# biointerfaceController_pcb_Sens.net
KiCad netlist of a schematic drawn in Altium Designer
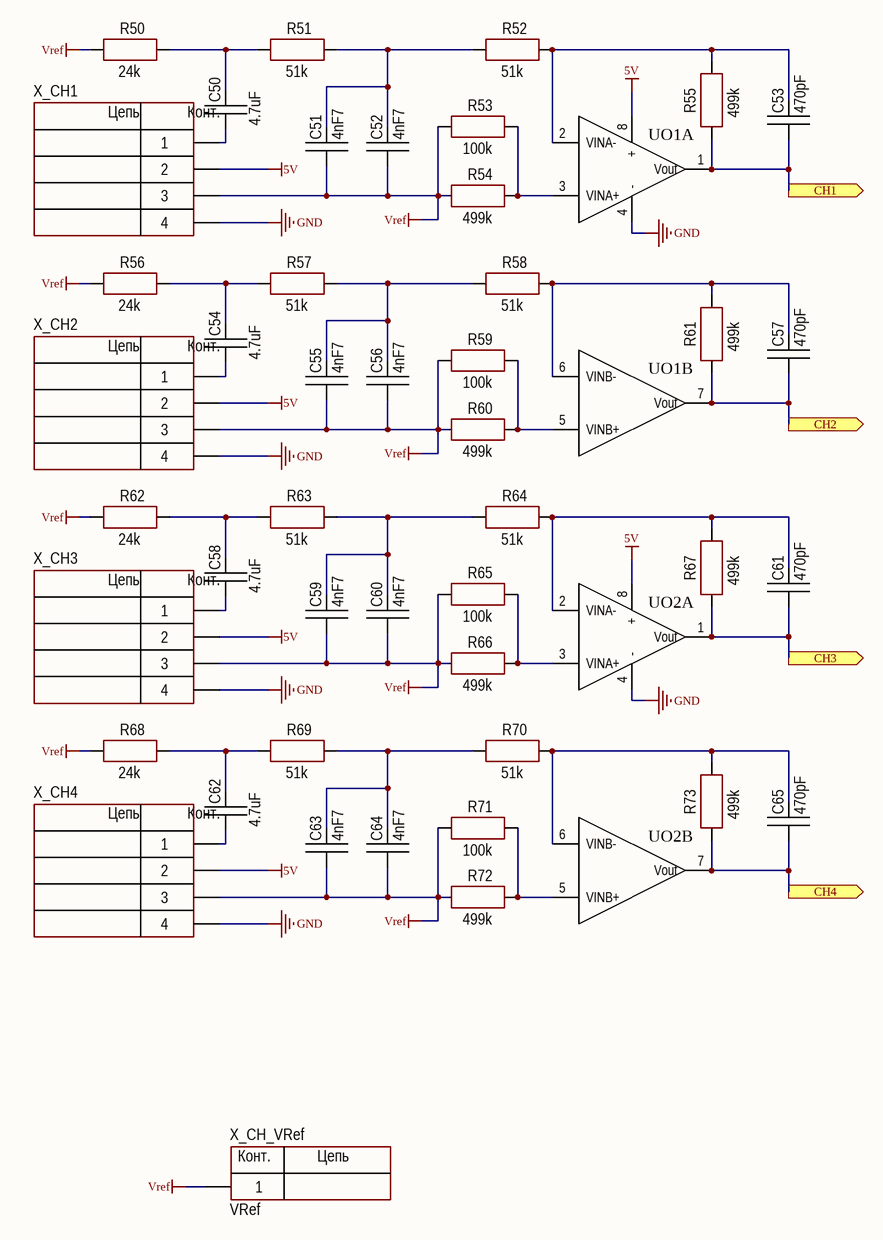
[diagram p0: biointerfaceController_pcb_Sens.SchDoc]

(export (version "E")
  (design (tool "Eeschema 10.0.6"))
  (components
    (comp (ref "C50")
      (value "4.7uF")
      (footprint "SMD-1206C")
      (libsource (lib "biointerfaceController_pcb") (part "Capacitor"))
    )
    (comp (ref "C51") (value "4nF7") (footprint "CH0402C") (libsource (lib "") (part "Capacitor_1")))
    (comp (ref "C52") (value "4nF7") (footprint "CH0402C") (libsource (lib "") (part "Capacitor_1")))
    (comp (ref "C53")
      (value "470pF")
      (footprint "CH0402C")
      (libsource (lib "biointerfaceController_pcb") (part "Capacitor"))
    )
    (comp (ref "C54")
      (value "4.7uF")
      (footprint "SMD-1206C")
      (libsource (lib "biointerfaceController_pcb") (part "Capacitor"))
    )
    (comp (ref "C55")
      (value "4nF7")
      (footprint "CH0402C")
      (libsource (lib "biointerfaceController_pcb") (part "Capacitor"))
    )
    (comp (ref "C56")
      (value "4nF7")
      (footprint "CH0402C")
      (libsource (lib "biointerfaceController_pcb") (part "Capacitor"))
    )
    (comp (ref "C57")
      (value "470pF")
      (footprint "CH0402C")
      (libsource (lib "biointerfaceController_pcb") (part "Capacitor"))
    )
    (comp (ref "C58")
      (value "4.7uF")
      (footprint "SMD-1206C")
      (libsource (lib "biointerfaceController_pcb") (part "Capacitor"))
    )
    (comp (ref "C59")
      (value "4nF7")
      (footprint "CH0402C")
      (libsource (lib "biointerfaceController_pcb") (part "Capacitor"))
    )
    (comp (ref "C60")
      (value "4nF7")
      (footprint "CH0402C")
      (libsource (lib "biointerfaceController_pcb") (part "Capacitor"))
    )
    (comp (ref "C61")
      (value "470pF")
      (footprint "CH0402C")
      (libsource (lib "biointerfaceController_pcb") (part "Capacitor"))
    )
    (comp (ref "C62")
      (value "4.7uF")
      (footprint "SMD-1206C")
      (libsource (lib "biointerfaceController_pcb") (part "Capacitor"))
    )
    (comp (ref "C63")
      (value "4nF7")
      (footprint "CH0402C")
      (libsource (lib "biointerfaceController_pcb") (part "Capacitor"))
    )
    (comp (ref "C64")
      (value "4nF7")
      (footprint "CH0402C")
      (libsource (lib "biointerfaceController_pcb") (part "Capacitor"))
    )
    (comp (ref "C65")
      (value "470pF")
      (footprint "CH0402C")
      (libsource (lib "biointerfaceController_pcb") (part "Capacitor"))
    )
    (comp (ref "R50")
      (value "24k")
      (footprint "CH0402R")
      (libsource (lib "biointerfaceController_pcb") (part "Resistor"))
    )
    (comp (ref "R51")
      (value "51k")
      (footprint "CH0402R")
      (libsource (lib "biointerfaceController_pcb") (part "Resistor"))
    )
    (comp (ref "R52")
      (value "51k")
      (footprint "CH0402R")
      (libsource (lib "biointerfaceController_pcb") (part "Resistor"))
    )
    (comp (ref "R53")
      (value "100k")
      (footprint "CH0402R")
      (libsource (lib "biointerfaceController_pcb") (part "Resistor"))
    )
    (comp (ref "R54")
      (value "499k")
      (footprint "CH0402R")
      (libsource (lib "biointerfaceController_pcb") (part "Resistor"))
    )
    (comp (ref "R55") (value "499k") (footprint "CH0402R") (libsource (lib "") (part "Resistor_1")))
    (comp (ref "R56")
      (value "24k")
      (footprint "CH0402R")
      (libsource (lib "biointerfaceController_pcb") (part "Resistor"))
    )
    (comp (ref "R57")
      (value "51k")
      (footprint "CH0402R")
      (libsource (lib "biointerfaceController_pcb") (part "Resistor"))
    )
    (comp (ref "R58")
      (value "51k")
      (footprint "CH0402R")
      (libsource (lib "biointerfaceController_pcb") (part "Resistor"))
    )
    (comp (ref "R59")
      (value "100k")
      (footprint "CH0402R")
      (libsource (lib "biointerfaceController_pcb") (part "Resistor"))
    )
    (comp (ref "R60")
      (value "499k")
      (footprint "CH0402R")
      (libsource (lib "biointerfaceController_pcb") (part "Resistor"))
    )
    (comp (ref "R61") (value "499k") (footprint "CH0402R") (libsource (lib "") (part "Resistor_1")))
    (comp (ref "R62")
      (value "24k")
      (footprint "CH0402R")
      (libsource (lib "biointerfaceController_pcb") (part "Resistor"))
    )
    (comp (ref "R63")
      (value "51k")
      (footprint "CH0402R")
      (libsource (lib "biointerfaceController_pcb") (part "Resistor"))
    )
    (comp (ref "R64")
      (value "51k")
      (footprint "CH0402R")
      (libsource (lib "biointerfaceController_pcb") (part "Resistor"))
    )
    (comp (ref "R65")
      (value "100k")
      (footprint "CH0402R")
      (libsource (lib "biointerfaceController_pcb") (part "Resistor"))
    )
    (comp (ref "R66")
      (value "499k")
      (footprint "CH0402R")
      (libsource (lib "biointerfaceController_pcb") (part "Resistor"))
    )
    (comp (ref "R67") (value "499k") (footprint "CH0402R") (libsource (lib "") (part "Resistor_1")))
    (comp (ref "R68")
      (value "24k")
      (footprint "CH0402R")
      (libsource (lib "biointerfaceController_pcb") (part "Resistor"))
    )
    (comp (ref "R69")
      (value "51k")
      (footprint "CH0402R")
      (libsource (lib "biointerfaceController_pcb") (part "Resistor"))
    )
    (comp (ref "R70")
      (value "51k")
      (footprint "CH0402R")
      (libsource (lib "biointerfaceController_pcb") (part "Resistor"))
    )
    (comp (ref "R71")
      (value "100k")
      (footprint "CH0402R")
      (libsource (lib "biointerfaceController_pcb") (part "Resistor"))
    )
    (comp (ref "R72")
      (value "499k")
      (footprint "CH0402R")
      (libsource (lib "biointerfaceController_pcb") (part "Resistor"))
    )
    (comp (ref "R73") (value "499k") (footprint "CH0402R") (libsource (lib "") (part "Resistor_1")))
    (comp (ref "UO1")
      (value "MCP6L02T-E/MS")
      (footprint "SOP65P490X110-8N")
      (fields (field (name "COPYRIGHT") "Copyright (C) 2018 Accelerated Designs. All rights reserved"))
      (libsource (lib "biointerfaceController_pcb") (part "MCP6L02T-E/MS"))
    )
    (comp (ref "UO2")
      (value "MCP6L02T-E/MS")
      (footprint "SOP65P490X110-8N")
      (fields (field (name "COPYRIGHT") "Copyright (C) 2018 Accelerated Designs. All rights reserved"))
      (libsource (lib "biointerfaceController_pcb") (part "MCP6L02T-E/MS"))
    )
    (comp (ref "X_CH1")
      (value "*")
      (footprint "JSTIC_Molex_125")
      (libsource (lib "biointerfaceController_pcb") (part "Connector-4"))
    )
    (comp (ref "X_CH2")
      (value "*")
      (footprint "JSTIC_Molex_125")
      (libsource (lib "biointerfaceController_pcb") (part "Connector-4"))
    )
    (comp (ref "X_CH3")
      (value "*")
      (footprint "JSTIC_Molex_125")
      (libsource (lib "biointerfaceController_pcb") (part "Connector-4"))
    )
    (comp (ref "X_CH4")
      (value "*")
      (footprint "JSTIC_Molex_125")
      (libsource (lib "biointerfaceController_pcb") (part "Connector-4"))
    )
    (comp (ref "X_CH_VRef")
      (value "VRef")
      (footprint "CON: PADS 1x1mm")
      (libsource (lib "biointerfaceController_pcb") (part "1-Connector"))
    )
  )
  (nets
    (net (code "1") (name "/CH1") (class "Default")
      (node (ref "C53") (pin "1") (pinfunction "1_1") (pintype "passive"))
      (node (ref "R55") (pin "1") (pinfunction "1_1") (pintype "passive"))
      (node (ref "UO1") (pin "1") (pinfunction "Vout_1") (pintype "passive"))
    )
    (net (code "2") (name "/CH2") (class "Default")
      (node (ref "C57") (pin "1") (pinfunction "1_1") (pintype "passive"))
      (node (ref "R61") (pin "1") (pinfunction "1_1") (pintype "passive"))
      (node (ref "UO1") (pin "7") (pinfunction "Vout_7") (pintype "passive"))
    )
    (net (code "3") (name "/CH3") (class "Default")
      (node (ref "C61") (pin "1") (pinfunction "1_1") (pintype "passive"))
      (node (ref "R67") (pin "1") (pinfunction "1_1") (pintype "passive"))
      (node (ref "UO2") (pin "1") (pinfunction "Vout_1") (pintype "passive"))
    )
    (net (code "4") (name "/CH4") (class "Default")
      (node (ref "C65") (pin "1") (pinfunction "1_1") (pintype "passive"))
      (node (ref "R73") (pin "1") (pinfunction "1_1") (pintype "passive"))
      (node (ref "UO2") (pin "7") (pinfunction "Vout_7") (pintype "passive"))
    )
    (net (code "5") (name "5V") (class "Default")
      (node (ref "UO1") (pin "8") (pinfunction "+_8") (pintype "passive"))
      (node (ref "UO2") (pin "8") (pinfunction "+_8") (pintype "passive"))
      (node (ref "X_CH1") (pin "2") (pinfunction "2_2") (pintype "passive"))
      (node (ref "X_CH2") (pin "2") (pinfunction "2_2") (pintype "passive"))
      (node (ref "X_CH3") (pin "2") (pinfunction "2_2") (pintype "passive"))
      (node (ref "X_CH4") (pin "2") (pinfunction "2_2") (pintype "passive"))
    )
    (net (code "6") (name "GND") (class "Default")
      (node (ref "UO1") (pin "4") (pinfunction "-_4") (pintype "passive"))
      (node (ref "UO2") (pin "4") (pinfunction "-_4") (pintype "passive"))
      (node (ref "X_CH1") (pin "4") (pinfunction "4_4") (pintype "power_in"))
      (node (ref "X_CH2") (pin "4") (pinfunction "4_4") (pintype "power_in"))
      (node (ref "X_CH3") (pin "4") (pinfunction "4_4") (pintype "power_in"))
      (node (ref "X_CH4") (pin "4") (pinfunction "4_4") (pintype "power_in"))
    )
    (net (code "7") (name "Net-(C50-Pad1)") (class "Default")
      (node (ref "C50") (pin "1") (pinfunction "1_1") (pintype "passive"))
      (node (ref "X_CH1") (pin "1") (pinfunction "1_1") (pintype "passive"))
    )
    (net (code "8") (name "Net-(C50-Pad2)") (class "Default")
      (node (ref "C50") (pin "2") (pinfunction "2_2") (pintype "passive"))
      (node (ref "R50") (pin "2") (pinfunction "2_2") (pintype "passive"))
      (node (ref "R51") (pin "1") (pinfunction "1_1") (pintype "passive"))
    )
    (net (code "9") (name "Net-(C51-Pad2)") (class "Default")
      (node (ref "C51") (pin "2") (pinfunction "2_2") (pintype "passive"))
      (node (ref "C52") (pin "2") (pinfunction "2_2") (pintype "passive"))
      (node (ref "R51") (pin "2") (pinfunction "2_2") (pintype "passive"))
      (node (ref "R52") (pin "1") (pinfunction "1_1") (pintype "passive"))
    )
    (net (code "10") (name "Net-(C54-Pad1)") (class "Default")
      (node (ref "C54") (pin "1") (pinfunction "1_1") (pintype "passive"))
      (node (ref "X_CH2") (pin "1") (pinfunction "1_1") (pintype "passive"))
    )
    (net (code "11") (name "Net-(C54-Pad2)") (class "Default")
      (node (ref "C54") (pin "2") (pinfunction "2_2") (pintype "passive"))
      (node (ref "R56") (pin "2") (pinfunction "2_2") (pintype "passive"))
      (node (ref "R57") (pin "1") (pinfunction "1_1") (pintype "passive"))
    )
    (net (code "12") (name "Net-(C55-Pad2)") (class "Default")
      (node (ref "C55") (pin "2") (pinfunction "2_2") (pintype "passive"))
      (node (ref "C56") (pin "2") (pinfunction "2_2") (pintype "passive"))
      (node (ref "R57") (pin "2") (pinfunction "2_2") (pintype "passive"))
      (node (ref "R58") (pin "1") (pinfunction "1_1") (pintype "passive"))
    )
    (net (code "13") (name "Net-(C58-Pad1)") (class "Default")
      (node (ref "C58") (pin "1") (pinfunction "1_1") (pintype "passive"))
      (node (ref "X_CH3") (pin "1") (pinfunction "1_1") (pintype "passive"))
    )
    (net (code "14") (name "Net-(C58-Pad2)") (class "Default")
      (node (ref "C58") (pin "2") (pinfunction "2_2") (pintype "passive"))
      (node (ref "R62") (pin "2") (pinfunction "2_2") (pintype "passive"))
      (node (ref "R63") (pin "1") (pinfunction "1_1") (pintype "passive"))
    )
    (net (code "15") (name "Net-(C59-Pad2)") (class "Default")
      (node (ref "C59") (pin "2") (pinfunction "2_2") (pintype "passive"))
      (node (ref "C60") (pin "2") (pinfunction "2_2") (pintype "passive"))
      (node (ref "R63") (pin "2") (pinfunction "2_2") (pintype "passive"))
      (node (ref "R64") (pin "1") (pinfunction "1_1") (pintype "passive"))
    )
    (net (code "16") (name "Net-(C62-Pad1)") (class "Default")
      (node (ref "C62") (pin "1") (pinfunction "1_1") (pintype "passive"))
      (node (ref "X_CH4") (pin "1") (pinfunction "1_1") (pintype "passive"))
    )
    (net (code "17") (name "Net-(C62-Pad2)") (class "Default")
      (node (ref "C62") (pin "2") (pinfunction "2_2") (pintype "passive"))
      (node (ref "R68") (pin "2") (pinfunction "2_2") (pintype "passive"))
      (node (ref "R69") (pin "1") (pinfunction "1_1") (pintype "passive"))
    )
    (net (code "18") (name "Net-(C63-Pad2)") (class "Default")
      (node (ref "C63") (pin "2") (pinfunction "2_2") (pintype "passive"))
      (node (ref "C64") (pin "2") (pinfunction "2_2") (pintype "passive"))
      (node (ref "R69") (pin "2") (pinfunction "2_2") (pintype "passive"))
      (node (ref "R70") (pin "1") (pinfunction "1_1") (pintype "passive"))
    )
    (net (code "19") (name "Net-(UO1A-VINA+)") (class "Default")
      (node (ref "R53") (pin "2") (pinfunction "2_2") (pintype "passive"))
      (node (ref "R54") (pin "2") (pinfunction "2_2") (pintype "passive"))
      (node (ref "UO1") (pin "3") (pinfunction "VINA+_3") (pintype "passive"))
    )
    (net (code "20") (name "Net-(UO1A-VINA-)") (class "Default")
      (node (ref "C53") (pin "2") (pinfunction "2_2") (pintype "passive"))
      (node (ref "R52") (pin "2") (pinfunction "2_2") (pintype "passive"))
      (node (ref "R55") (pin "2") (pinfunction "2_2") (pintype "passive"))
      (node (ref "UO1") (pin "2") (pinfunction "VINA-_2") (pintype "passive"))
    )
    (net (code "21") (name "Net-(UO1B-VINB+)") (class "Default")
      (node (ref "R59") (pin "2") (pinfunction "2_2") (pintype "passive"))
      (node (ref "R60") (pin "2") (pinfunction "2_2") (pintype "passive"))
      (node (ref "UO1") (pin "5") (pinfunction "VINB+_5") (pintype "passive"))
    )
    (net (code "22") (name "Net-(UO1B-VINB-)") (class "Default")
      (node (ref "C57") (pin "2") (pinfunction "2_2") (pintype "passive"))
      (node (ref "R58") (pin "2") (pinfunction "2_2") (pintype "passive"))
      (node (ref "R61") (pin "2") (pinfunction "2_2") (pintype "passive"))
      (node (ref "UO1") (pin "6") (pinfunction "VINB-_6") (pintype "passive"))
    )
    (net (code "23") (name "Net-(UO2A-VINA+)") (class "Default")
      (node (ref "R65") (pin "2") (pinfunction "2_2") (pintype "passive"))
      (node (ref "R66") (pin "2") (pinfunction "2_2") (pintype "passive"))
      (node (ref "UO2") (pin "3") (pinfunction "VINA+_3") (pintype "passive"))
    )
    (net (code "24") (name "Net-(UO2A-VINA-)") (class "Default")
      (node (ref "C61") (pin "2") (pinfunction "2_2") (pintype "passive"))
      (node (ref "R64") (pin "2") (pinfunction "2_2") (pintype "passive"))
      (node (ref "R67") (pin "2") (pinfunction "2_2") (pintype "passive"))
      (node (ref "UO2") (pin "2") (pinfunction "VINA-_2") (pintype "passive"))
    )
    (net (code "25") (name "Net-(UO2B-VINB+)") (class "Default")
      (node (ref "R71") (pin "2") (pinfunction "2_2") (pintype "passive"))
      (node (ref "R72") (pin "2") (pinfunction "2_2") (pintype "passive"))
      (node (ref "UO2") (pin "5") (pinfunction "VINB+_5") (pintype "passive"))
    )
    (net (code "26") (name "Net-(UO2B-VINB-)") (class "Default")
      (node (ref "C65") (pin "2") (pinfunction "2_2") (pintype "passive"))
      (node (ref "R70") (pin "2") (pinfunction "2_2") (pintype "passive"))
      (node (ref "R73") (pin "2") (pinfunction "2_2") (pintype "passive"))
      (node (ref "UO2") (pin "6") (pinfunction "VINB-_6") (pintype "passive"))
    )
    (net (code "27") (name "Vref") (class "Default")
      (node (ref "C51") (pin "1") (pinfunction "1_1") (pintype "passive"))
      (node (ref "C52") (pin "1") (pinfunction "1_1") (pintype "passive"))
      (node (ref "C55") (pin "1") (pinfunction "1_1") (pintype "passive"))
      (node (ref "C56") (pin "1") (pinfunction "1_1") (pintype "passive"))
      (node (ref "C59") (pin "1") (pinfunction "1_1") (pintype "passive"))
      (node (ref "C60") (pin "1") (pinfunction "1_1") (pintype "passive"))
      (node (ref "C63") (pin "1") (pinfunction "1_1") (pintype "passive"))
      (node (ref "C64") (pin "1") (pinfunction "1_1") (pintype "passive"))
      (node (ref "R50") (pin "1") (pinfunction "1_1") (pintype "passive"))
      (node (ref "R53") (pin "1") (pinfunction "1_1") (pintype "passive"))
      (node (ref "R54") (pin "1") (pinfunction "1_1") (pintype "passive"))
      (node (ref "R56") (pin "1") (pinfunction "1_1") (pintype "passive"))
      (node (ref "R59") (pin "1") (pinfunction "1_1") (pintype "passive"))
      (node (ref "R60") (pin "1") (pinfunction "1_1") (pintype "passive"))
      (node (ref "R62") (pin "1") (pinfunction "1_1") (pintype "passive"))
      (node (ref "R65") (pin "1") (pinfunction "1_1") (pintype "passive"))
      (node (ref "R66") (pin "1") (pinfunction "1_1") (pintype "passive"))
      (node (ref "R68") (pin "1") (pinfunction "1_1") (pintype "passive"))
      (node (ref "R71") (pin "1") (pinfunction "1_1") (pintype "passive"))
      (node (ref "R72") (pin "1") (pinfunction "1_1") (pintype "passive"))
      (node (ref "X_CH1") (pin "3") (pinfunction "3_3") (pintype "power_in"))
      (node (ref "X_CH2") (pin "3") (pinfunction "3_3") (pintype "power_in"))
      (node (ref "X_CH3") (pin "3") (pinfunction "3_3") (pintype "power_in"))
      (node (ref "X_CH4") (pin "3") (pinfunction "3_3") (pintype "power_in"))
      (node (ref "X_CH_VRef") (pin "1") (pinfunction "1_1") (pintype "passive"))
    )
  )
)
